# 1.net
KiCad netlist of a schematic drawn in Altium Designer
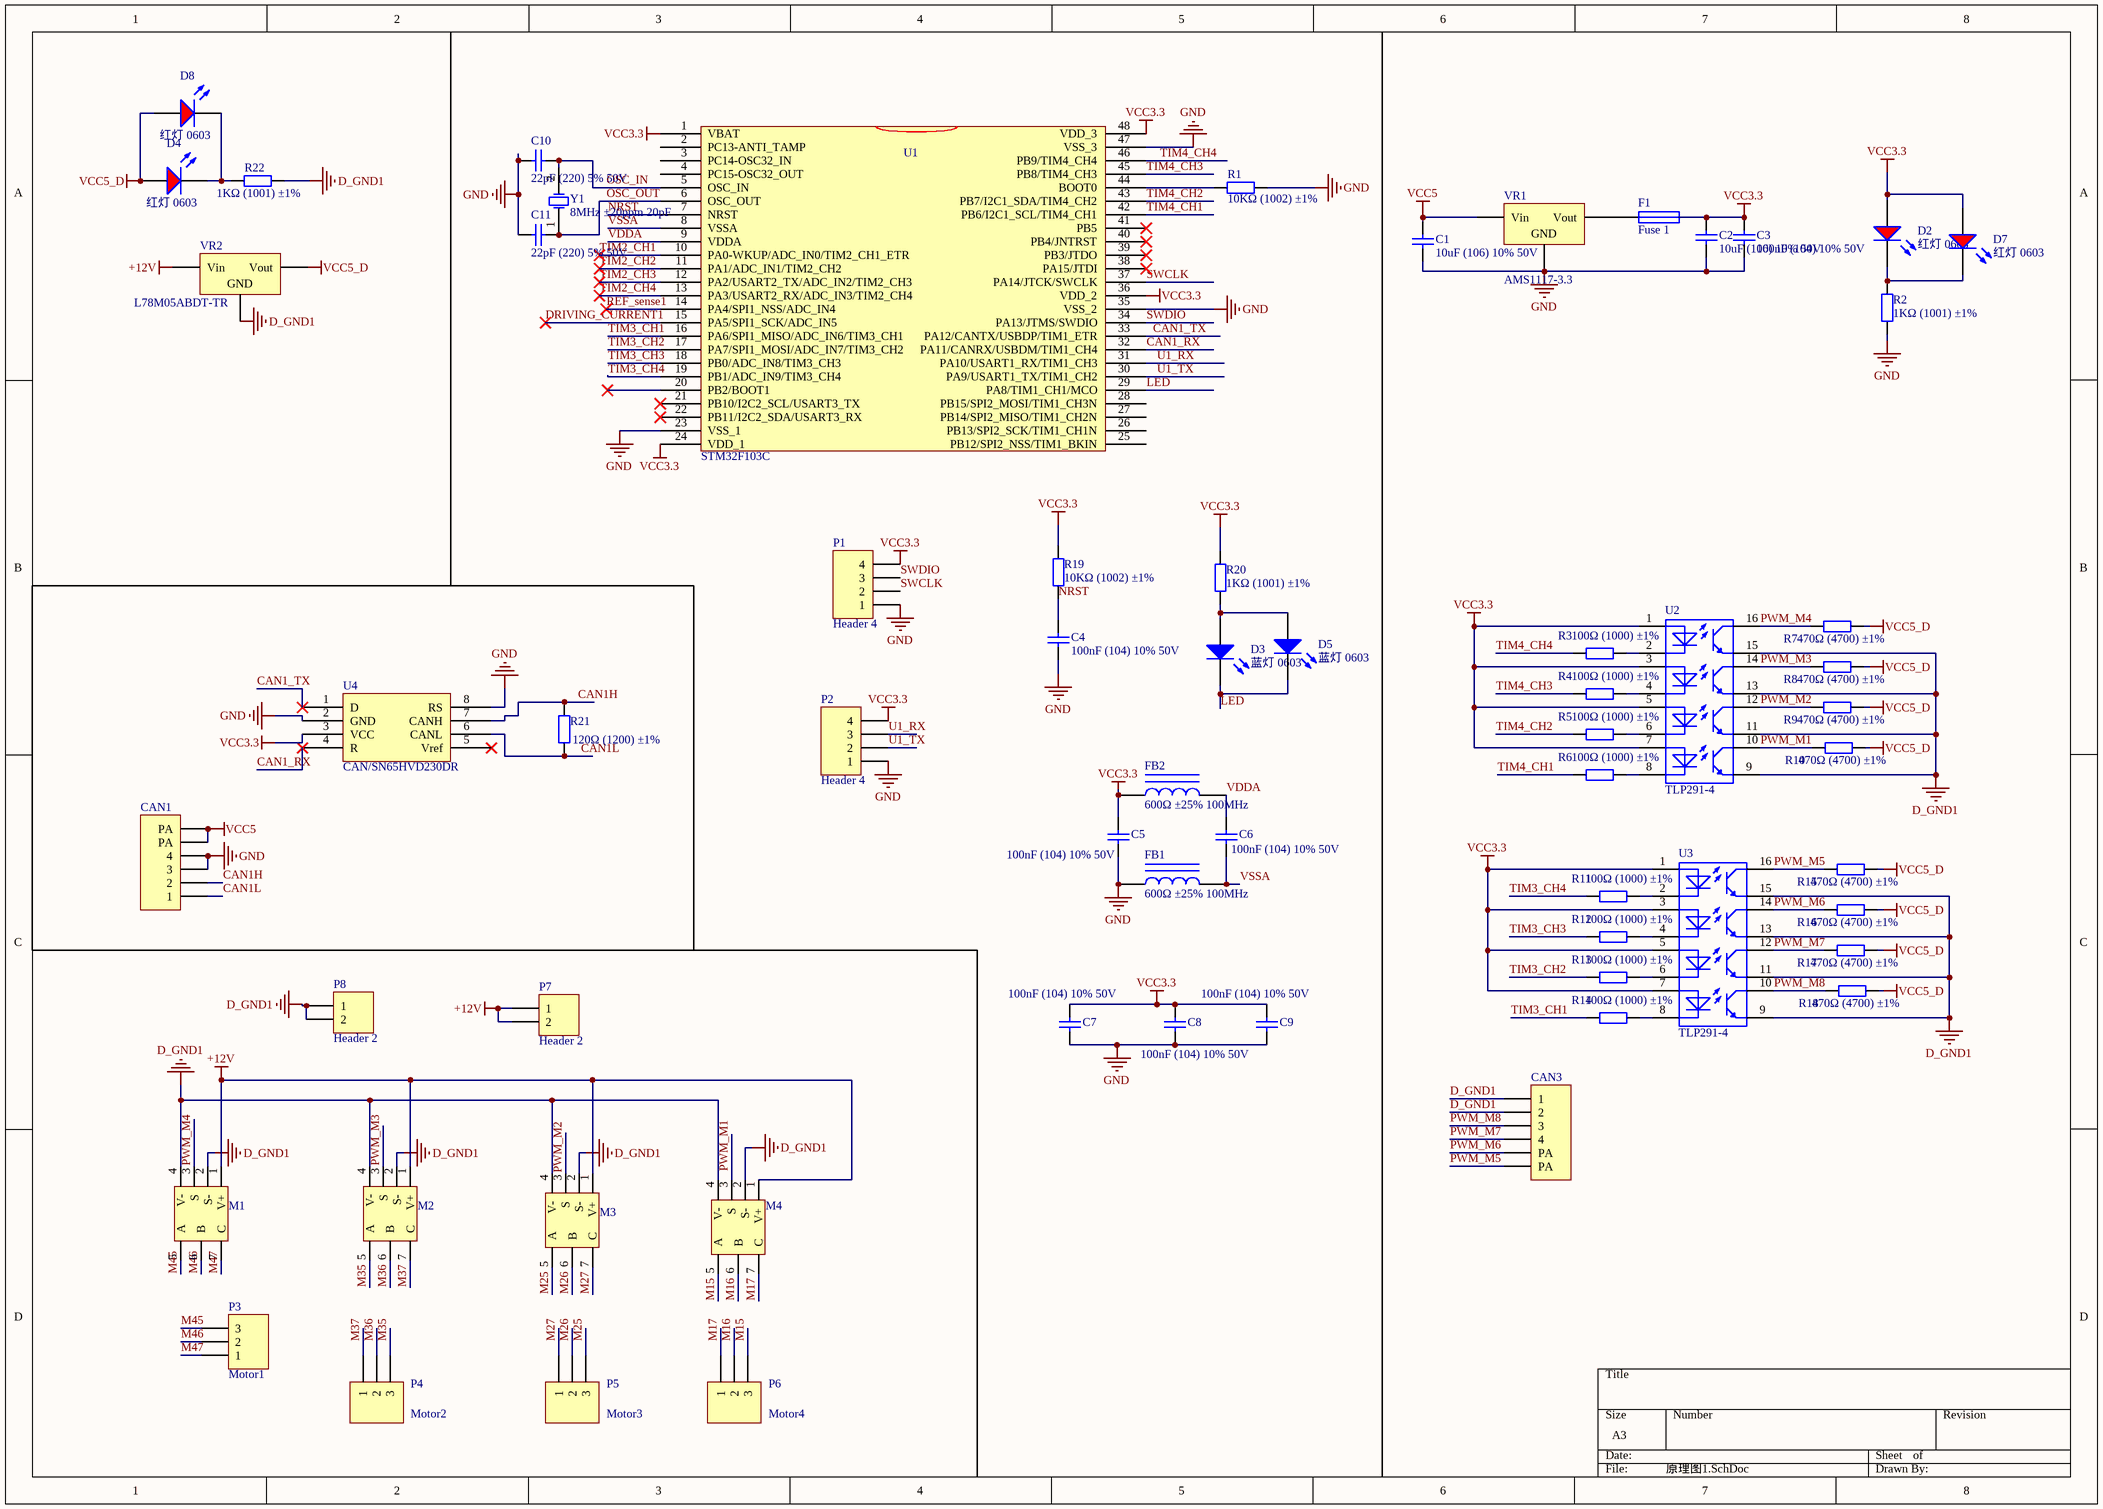
[diagram p0: 原理图1.SchDoc]

(export (version "E")
  (design (tool "Eeschema 10.0.6"))
  (components
    (comp (ref "C1")
      (value "10uF (106) 10% 50V")
      (footprint "0603_C")
      (description "贴片电容")
      (libsource (lib "Miscellaneous Devices LC") (part "1206 10uF (106) 10% 50V"))
    )
    (comp (ref "C2")
      (value "10uF (106) 10% 50V")
      (footprint "0603_C")
      (description "贴片电容")
      (libsource (lib "Miscellaneous Devices LC") (part "1206 10uF (106) 10% 50V"))
    )
    (comp (ref "C3")
      (value "100nF (104) 10% 50V")
      (footprint "0603_C")
      (description "贴片电容")
      (libsource (lib "Miscellaneous Devices LC") (part "0603 100nF (104) 10% 50V"))
    )
    (comp (ref "C4")
      (value "100nF (104) 10% 50V")
      (footprint "0603_C")
      (description "贴片电容")
      (libsource (lib "Miscellaneous Devices LC") (part "0603 100nF (104) 10% 50V"))
    )
    (comp (ref "C5")
      (value "100nF (104) 10% 50V")
      (footprint "0603_C")
      (description "贴片电容")
      (libsource (lib "Miscellaneous Devices LC") (part "0603 100nF (104) 10% 50V"))
    )
    (comp (ref "C6")
      (value "100nF (104) 10% 50V")
      (footprint "0603_C")
      (description "贴片电容")
      (libsource (lib "Miscellaneous Devices LC") (part "0603 100nF (104) 10% 50V"))
    )
    (comp (ref "C7")
      (value "100nF (104) 10% 50V")
      (footprint "0603_C")
      (description "贴片电容")
      (libsource (lib "Miscellaneous Devices LC") (part "0603 100nF (104) 10% 50V"))
    )
    (comp (ref "C8")
      (value "100nF (104) 10% 50V")
      (footprint "0603_C")
      (description "贴片电容")
      (libsource (lib "Miscellaneous Devices LC") (part "0603 100nF (104) 10% 50V"))
    )
    (comp (ref "C9")
      (value "100nF (104) 10% 50V")
      (footprint "0603_C")
      (description "贴片电容")
      (libsource (lib "Miscellaneous Devices LC") (part "0603 100nF (104) 10% 50V"))
    )
    (comp (ref "C10")
      (value "22pF (220) 5% 50V")
      (footprint "0603_C")
      (description "贴片电容")
      (libsource (lib "AD封装2018.9.19Miscellaneous Devices LC") (part "0805 22pF (220) 5% 50V"))
    )
    (comp (ref "C11")
      (value "22pF (220) 5% 50V")
      (footprint "0603_C")
      (description "贴片电容")
      (libsource (lib "AD封装2018.9.19Miscellaneous Devices LC") (part "0805 22pF (220) 5% 50V"))
    )
    (comp (ref "CAN1")
      (value "Header 6")
      (footprint "Modolex_6P")
      (description "Header, 6-Pin")
      (fields (field (name "PUBLISHER") "Altium Limited"))
      (libsource (lib "roobmaster_1") (part "Header 6"))
    )
    (comp (ref "CAN3")
      (value "Header 6")
      (footprint "Modolex_6P")
      (description "Header, 6-Pin")
      (fields (field (name "PUBLISHER") "Altium Limited"))
      (libsource (lib "无刷电机驱动") (part "Header 6"))
    )
    (comp (ref "D2")
      (value "红灯 0603")
      (footprint "0603_LED_S1")
      (description "发光二极管")
      (libsource (lib "Miscellaneous Devices LC") (part "0603 红灯"))
    )
    (comp (ref "D3")
      (value "蓝灯 0603")
      (footprint "0603_LED_S1")
      (description "发光二极管")
      (libsource (lib "Miscellaneous Devices LC") (part "0603 蓝灯"))
    )
    (comp (ref "D4")
      (value "红灯 0603")
      (footprint "0603_LED_S1")
      (description "发光二极管")
      (libsource (lib "Miscellaneous Devices LC") (part "0603 红灯"))
    )
    (comp (ref "D5")
      (value "蓝灯 0603")
      (footprint "0603_LED_S1")
      (description "发光二极管")
      (libsource (lib "Miscellaneous Devices LC") (part "0603 蓝灯"))
    )
    (comp (ref "D7")
      (value "红灯 0603")
      (footprint "0603_LED_S1")
      (description "发光二极管")
      (libsource (lib "Miscellaneous Devices LC") (part "0603 红灯"))
    )
    (comp (ref "D8")
      (value "红灯 0603")
      (footprint "0603_LED_S1")
      (description "发光二极管")
      (libsource (lib "Miscellaneous Devices LC") (part "0603 红灯"))
    )
    (comp (ref "F1")
      (value "Fuse 1")
      (footprint "6-0805_M")
      (description "Fuse")
      (fields (field (name "PUBLISHER") "Altium Limited"))
      (libsource (lib "Miscellaneous Devices") (part "Fuse 1"))
    )
    (comp (ref "FB1")
      (value "600Ω ±25% 100MHz")
      (footprint "0603_L")
      (description "贴片磁珠")
      (libsource (lib "Miscellaneous Devices LC") (part "0805 600Ω 25% 100MHz"))
    )
    (comp (ref "FB2")
      (value "600Ω ±25% 100MHz")
      (footprint "0603_L")
      (description "贴片磁珠")
      (libsource (lib "Miscellaneous Devices LC") (part "0805 600Ω 25% 100MHz"))
    )
    (comp (ref "M1")
      (value "HOBBYWING_FPV")
      (footprint "HOBBYWING_WING20A/30A")
      (libsource (lib "无刷电机驱动") (part "HOBBYWING_FPV"))
    )
    (comp (ref "M2")
      (value "HOBBYWING_FPV")
      (footprint "HOBBYWING_WING20A/30A")
      (libsource (lib "无刷电机驱动") (part "HOBBYWING_FPV"))
    )
    (comp (ref "M3")
      (value "HOBBYWING_FPV")
      (footprint "HOBBYWING_WING20A/30A")
      (libsource (lib "无刷电机驱动") (part "HOBBYWING_FPV"))
    )
    (comp (ref "M4")
      (value "~")
      (footprint "HOBBYWING_WING20A/30A")
      (libsource (lib "无刷电机驱动20180528") (part "HOBBYWING_FPV"))
    )
    (comp (ref "P1")
      (value "Header 4")
      (footprint "Molex-4")
      (description "Header, 4-Pin")
      (fields (field (name "PUBLISHER") "Altium Limited"))
      (libsource (lib "Miscellaneous Connectors") (part "Header 4"))
    )
    (comp (ref "P2")
      (value "Header 4")
      (footprint "Molex-4")
      (description "Header, 4-Pin")
      (fields (field (name "PUBLISHER") "Altium Limited"))
      (libsource (lib "Miscellaneous Connectors") (part "Header 4"))
    )
    (comp (ref "P3")
      (value "Motor1")
      (footprint "11:1")
      (description "Header, 3-Pin")
      (fields (field (name "PUBLISHER") "Altium Limited"))
      (libsource (lib "") (part "Header 3_1"))
    )
    (comp (ref "P4")
      (value "Motor2")
      (footprint "11:1")
      (description "Header, 3-Pin")
      (fields (field (name "PUBLISHER") "Altium Limited"))
      (libsource (lib "Miscellaneous Connectors") (part "Header 3"))
    )
    (comp (ref "P5")
      (value "Motor3")
      (footprint "11:1")
      (description "Header, 3-Pin")
      (fields (field (name "PUBLISHER") "Altium Limited"))
      (libsource (lib "Miscellaneous Connectors") (part "Header 3"))
    )
    (comp (ref "P6")
      (value "Motor4")
      (footprint "11:1")
      (description "Header, 3-Pin")
      (fields (field (name "PUBLISHER") "Altium Limited"))
      (libsource (lib "Miscellaneous Connectors") (part "Header 3"))
    )
    (comp (ref "P7")
      (value "Header 2")
      (footprint "XT30 - 2")
      (description "Header, 2-Pin")
      (fields (field (name "PUBLISHER") "Altium Limited"))
      (libsource (lib "Miscellaneous Connectors") (part "Header 2"))
    )
    (comp (ref "P8")
      (value "Header 2")
      (footprint "XT30 - 2")
      (description "Header, 2-Pin")
      (fields (field (name "PUBLISHER") "Altium Limited"))
      (libsource (lib "Miscellaneous Connectors") (part "Header 2"))
    )
    (comp (ref "R1")
      (value "10KΩ (1002) ±1%")
      (footprint "0603_R")
      (description "贴片电阻")
      (libsource (lib "") (part "0603 10KΩ (1002) 1%_1"))
    )
    (comp (ref "R2")
      (value "1KΩ (1001) ±1%")
      (footprint "0603_R")
      (description "贴片电阻")
      (libsource (lib "") (part "0603 1KΩ (1001) 1%_1"))
    )
    (comp (ref "R3")
      (value "100Ω (1000) ±1%")
      (footprint "0603_R")
      (description "贴片电阻")
      (libsource (lib "Miscellaneous Devices LC") (part "0603 100Ω (1000) 1%"))
    )
    (comp (ref "R4")
      (value "100Ω (1000) ±1%")
      (footprint "0603_R")
      (description "贴片电阻")
      (libsource (lib "Miscellaneous Devices LC") (part "0603 100Ω (1000) 1%"))
    )
    (comp (ref "R5")
      (value "100Ω (1000) ±1%")
      (footprint "0603_R")
      (description "贴片电阻")
      (libsource (lib "Miscellaneous Devices LC") (part "0603 100Ω (1000) 1%"))
    )
    (comp (ref "R6")
      (value "100Ω (1000) ±1%")
      (footprint "0603_R")
      (description "贴片电阻")
      (libsource (lib "Miscellaneous Devices LC") (part "0603 100Ω (1000) 1%"))
    )
    (comp (ref "R7")
      (value "470Ω (4700) ±1%")
      (footprint "0603_R")
      (description "贴片电阻")
      (libsource (lib "Miscellaneous Devices LC") (part "0603 470Ω (4700) 1%"))
    )
    (comp (ref "R8")
      (value "470Ω (4700) ±1%")
      (footprint "0603_R")
      (description "贴片电阻")
      (libsource (lib "Miscellaneous Devices LC") (part "0603 470Ω (4700) 1%"))
    )
    (comp (ref "R9")
      (value "470Ω (4700) ±1%")
      (footprint "0603_R")
      (description "贴片电阻")
      (libsource (lib "Miscellaneous Devices LC") (part "0603 470Ω (4700) 1%"))
    )
    (comp (ref "R10")
      (value "470Ω (4700) ±1%")
      (footprint "0603_R")
      (description "贴片电阻")
      (libsource (lib "Miscellaneous Devices LC") (part "0603 470Ω (4700) 1%"))
    )
    (comp (ref "R11")
      (value "100Ω (1000) ±1%")
      (footprint "0603_R")
      (description "贴片电阻")
      (libsource (lib "Miscellaneous Devices LC") (part "0603 100Ω (1000) 1%"))
    )
    (comp (ref "R12")
      (value "100Ω (1000) ±1%")
      (footprint "0603_R")
      (description "贴片电阻")
      (libsource (lib "Miscellaneous Devices LC") (part "0603 100Ω (1000) 1%"))
    )
    (comp (ref "R13")
      (value "100Ω (1000) ±1%")
      (footprint "0603_R")
      (description "贴片电阻")
      (libsource (lib "Miscellaneous Devices LC") (part "0603 100Ω (1000) 1%"))
    )
    (comp (ref "R14")
      (value "100Ω (1000) ±1%")
      (footprint "0603_R")
      (description "贴片电阻")
      (libsource (lib "Miscellaneous Devices LC") (part "0603 100Ω (1000) 1%"))
    )
    (comp (ref "R15")
      (value "470Ω (4700) ±1%")
      (footprint "0603_R")
      (description "贴片电阻")
      (libsource (lib "Miscellaneous Devices LC") (part "0603 470Ω (4700) 1%"))
    )
    (comp (ref "R16")
      (value "470Ω (4700) ±1%")
      (footprint "0603_R")
      (description "贴片电阻")
      (libsource (lib "Miscellaneous Devices LC") (part "0603 470Ω (4700) 1%"))
    )
    (comp (ref "R17")
      (value "470Ω (4700) ±1%")
      (footprint "0603_R")
      (description "贴片电阻")
      (libsource (lib "Miscellaneous Devices LC") (part "0603 470Ω (4700) 1%"))
    )
    (comp (ref "R18")
      (value "470Ω (4700) ±1%")
      (footprint "0603_R")
      (description "贴片电阻")
      (libsource (lib "Miscellaneous Devices LC") (part "0603 470Ω (4700) 1%"))
    )
    (comp (ref "R19")
      (value "10KΩ (1002) ±1%")
      (footprint "0603_R")
      (description "贴片电阻")
      (libsource (lib "Miscellaneous Devices LC") (part "0603 10KΩ (1002) 1%"))
    )
    (comp (ref "R20")
      (value "1KΩ (1001) ±1%")
      (footprint "0603_R")
      (description "贴片电阻")
      (libsource (lib "") (part "0603 1KΩ (1001) 1%_1"))
    )
    (comp (ref "R21")
      (value "120Ω (1200) ±1%")
      (footprint "0603_R")
      (description "贴片电阻")
      (libsource (lib "Miscellaneous Devices LC") (part "0603 120Ω (1200) 1%"))
    )
    (comp (ref "R22")
      (value "1KΩ (1001) ±1%")
      (footprint "0603_R")
      (description "贴片电阻")
      (libsource (lib "Miscellaneous Devices LC") (part "0603 1KΩ (1001) 1%"))
    )
    (comp (ref "U1")
      (value "STM32F103C")
      (footprint "LQFP-48_7x7x05P")
      (libsource (lib "my_lib") (part "STM32F103C"))
    )
    (comp (ref "U2")
      (value "TLP291-4")
      (footprint "LC-SOP-16_150mil")
      (libsource (lib "XQ_Library") (part "TLP521-4"))
    )
    (comp (ref "U3")
      (value "TLP291-4")
      (footprint "LC-SOP-16_150mil")
      (libsource (lib "XQ_Library") (part "TLP521-4"))
    )
    (comp (ref "U4")
      (value "CAN/SN65HVD230DR")
      (footprint "SOIC-8_150mil")
      (description "CAN")
      (libsource (lib "AD封装2018.9.19Miscellaneous Devices LC") (part "CAN/SN65HVD230DR_[C12084]"))
    )
    (comp (ref "VR1")
      (value "AMS1117-3.3")
      (footprint "SOT-223")
      (description "低压差线性稳压(LDO)")
      (libsource (lib "Miscellaneous Devices LC") (part "SOT-223 AMS1117-3.3"))
    )
    (comp (ref "VR2")
      (value "L78M05ABDT-TR")
      (footprint "TO-252-2-180")
      (description "低压差线性稳压(LDO)")
      (libsource (lib "Miscellaneous Devices LC") (part "TO-252-2 L78M05ABDT-TR"))
    )
    (comp (ref "Y1")
      (value "8MHz ±20ppm 20pF")
      (footprint "SMD-5032_2P")
      (description "贴片晶振")
      (libsource (lib "AD封装2018.9.19Miscellaneous Devices LC") (part "SMD-5032_2P 8MHz 20ppm 20pF"))
    )
  )
  (nets
    (net (code "1") (name "+12V") (class "Default")
      (node (ref "M1") (pin "1") (pinfunction "V+_1") (pintype "passive"))
      (node (ref "M2") (pin "1") (pinfunction "V+_1") (pintype "passive"))
      (node (ref "M3") (pin "1") (pinfunction "V+_1") (pintype "passive"))
      (node (ref "M4") (pin "1") (pinfunction "V+_1") (pintype "passive"))
      (node (ref "P7") (pin "1") (pinfunction "1_1") (pintype "passive"))
      (node (ref "P7") (pin "2") (pinfunction "2_2") (pintype "passive"))
      (node (ref "VR2") (pin "1") (pinfunction "Vin_1") (pintype "passive"))
    )
    (net (code "2") (name "/CAN1H") (class "Default")
      (node (ref "CAN1") (pin "2") (pinfunction "2_2") (pintype "passive"))
      (node (ref "R21") (pin "1") (pinfunction "1_1") (pintype "passive"))
      (node (ref "U4") (pin "7") (pinfunction "CANH_7") (pintype "passive"))
    )
    (net (code "3") (name "/CAN1L") (class "Default")
      (node (ref "CAN1") (pin "1") (pinfunction "1_1") (pintype "passive"))
      (node (ref "R21") (pin "2") (pinfunction "2_2") (pintype "passive"))
      (node (ref "U4") (pin "6") (pinfunction "CANL_6") (pintype "passive"))
    )
    (net (code "4") (name "/CAN1_RX") (class "Default")
      (node (ref "U1") (pin "32") (pinfunction "PA11/CANRX/USBDM/TIM1_CH4_32") (pintype "passive"))
      (node (ref "U4") (pin "4") (pinfunction "R_4") (pintype "passive"))
    )
    (net (code "5") (name "/CAN1_TX") (class "Default")
      (node (ref "U1") (pin "33") (pinfunction "PA12/CANTX/USBDP/TIM1_ETR_33") (pintype "passive"))
      (node (ref "U4") (pin "1") (pinfunction "D_1") (pintype "passive"))
    )
    (net (code "6") (name "/DRIVING_CURRENT1") (class "Default")
      (node (ref "U1") (pin "15") (pinfunction "PA5/SPI1_SCK/ADC_IN5_15") (pintype "passive+no_connect"))
    )
    (net (code "7") (name "/LED") (class "Default")
      (node (ref "D3") (pin "K") (pinfunction "K_K") (pintype "passive"))
      (node (ref "D5") (pin "K") (pinfunction "K_K") (pintype "passive"))
      (node (ref "U1") (pin "29") (pinfunction "PA8/TIM1_CH1/MCO_29") (pintype "passive"))
    )
    (net (code "8") (name "/M15") (class "Default")
      (node (ref "M4") (pin "5") (pinfunction "A_5") (pintype "passive"))
      (node (ref "P6") (pin "3") (pinfunction "3_3") (pintype "passive"))
    )
    (net (code "9") (name "/M16") (class "Default")
      (node (ref "M4") (pin "6") (pinfunction "B_6") (pintype "passive"))
      (node (ref "P6") (pin "2") (pinfunction "2_2") (pintype "passive"))
    )
    (net (code "10") (name "/M17") (class "Default")
      (node (ref "M4") (pin "7") (pinfunction "C_7") (pintype "passive"))
      (node (ref "P6") (pin "1") (pinfunction "1_1") (pintype "passive"))
    )
    (net (code "11") (name "/M25") (class "Default")
      (node (ref "M3") (pin "5") (pinfunction "A_5") (pintype "passive"))
      (node (ref "P5") (pin "3") (pinfunction "3_3") (pintype "passive"))
    )
    (net (code "12") (name "/M26") (class "Default")
      (node (ref "M3") (pin "6") (pinfunction "B_6") (pintype "passive"))
      (node (ref "P5") (pin "2") (pinfunction "2_2") (pintype "passive"))
    )
    (net (code "13") (name "/M27") (class "Default")
      (node (ref "M3") (pin "7") (pinfunction "C_7") (pintype "passive"))
      (node (ref "P5") (pin "1") (pinfunction "1_1") (pintype "passive"))
    )
    (net (code "14") (name "/M35") (class "Default")
      (node (ref "M2") (pin "5") (pinfunction "A_5") (pintype "passive"))
      (node (ref "P4") (pin "3") (pinfunction "3_3") (pintype "passive"))
    )
    (net (code "15") (name "/M36") (class "Default")
      (node (ref "M2") (pin "6") (pinfunction "B_6") (pintype "passive"))
      (node (ref "P4") (pin "2") (pinfunction "2_2") (pintype "passive"))
    )
    (net (code "16") (name "/M37") (class "Default")
      (node (ref "M2") (pin "7") (pinfunction "C_7") (pintype "passive"))
      (node (ref "P4") (pin "1") (pinfunction "1_1") (pintype "passive"))
    )
    (net (code "17") (name "/M45") (class "Default")
      (node (ref "M1") (pin "5") (pinfunction "A_5") (pintype "passive"))
      (node (ref "P3") (pin "3") (pinfunction "3_3") (pintype "passive"))
    )
    (net (code "18") (name "/M46") (class "Default")
      (node (ref "M1") (pin "6") (pinfunction "B_6") (pintype "passive"))
      (node (ref "P3") (pin "2") (pinfunction "2_2") (pintype "passive"))
    )
    (net (code "19") (name "/M47") (class "Default")
      (node (ref "M1") (pin "7") (pinfunction "C_7") (pintype "passive"))
      (node (ref "P3") (pin "1") (pinfunction "1_1") (pintype "passive"))
    )
    (net (code "20") (name "/NRST") (class "Default")
      (node (ref "C4") (pin "2") (pinfunction "2_2") (pintype "passive"))
      (node (ref "R19") (pin "1") (pinfunction "1_1") (pintype "passive"))
      (node (ref "U1") (pin "7") (pinfunction "NRST_7") (pintype "passive"))
    )
    (net (code "21") (name "/OSC_IN") (class "Default")
      (node (ref "C10") (pin "2") (pinfunction "2_2") (pintype "passive"))
      (node (ref "U1") (pin "5") (pinfunction "OSC_IN_5") (pintype "passive"))
      (node (ref "Y1") (pin "2") (pinfunction "OSC2_2") (pintype "passive"))
    )
    (net (code "22") (name "/OSC_OUT") (class "Default")
      (node (ref "C11") (pin "2") (pinfunction "2_2") (pintype "passive"))
      (node (ref "U1") (pin "6") (pinfunction "OSC_OUT_6") (pintype "passive"))
      (node (ref "Y1") (pin "1") (pinfunction "OSC1_1") (pintype "passive"))
    )
    (net (code "23") (name "/PWM_M1") (class "Default")
      (node (ref "M4") (pin "3") (pinfunction "S_3") (pintype "passive"))
      (node (ref "R10") (pin "1") (pinfunction "1_1") (pintype "passive"))
      (node (ref "U2") (pin "10") (pinfunction "10_10") (pintype "passive"))
    )
    (net (code "24") (name "/PWM_M2") (class "Default")
      (node (ref "M3") (pin "3") (pinfunction "S_3") (pintype "passive"))
      (node (ref "R9") (pin "1") (pinfunction "1_1") (pintype "passive"))
      (node (ref "U2") (pin "12") (pinfunction "12_12") (pintype "passive"))
    )
    (net (code "25") (name "/PWM_M3") (class "Default")
      (node (ref "M2") (pin "3") (pinfunction "S_3") (pintype "passive"))
      (node (ref "R8") (pin "1") (pinfunction "1_1") (pintype "passive"))
      (node (ref "U2") (pin "14") (pinfunction "14_14") (pintype "passive"))
    )
    (net (code "26") (name "/PWM_M4") (class "Default")
      (node (ref "M1") (pin "3") (pinfunction "S_3") (pintype "passive"))
      (node (ref "R7") (pin "1") (pinfunction "1_1") (pintype "passive"))
      (node (ref "U2") (pin "16") (pinfunction "16_16") (pintype "passive"))
    )
    (net (code "27") (name "/PWM_M5") (class "Default")
      (node (ref "CAN3") (pin "6") (pinfunction "PA_6") (pintype "passive"))
      (node (ref "R15") (pin "1") (pinfunction "1_1") (pintype "passive"))
      (node (ref "U3") (pin "16") (pinfunction "16_16") (pintype "passive"))
    )
    (net (code "28") (name "/PWM_M6") (class "Default")
      (node (ref "CAN3") (pin "5") (pinfunction "PA_5") (pintype "passive"))
      (node (ref "R16") (pin "1") (pinfunction "1_1") (pintype "passive"))
      (node (ref "U3") (pin "14") (pinfunction "14_14") (pintype "passive"))
    )
    (net (code "29") (name "/PWM_M7") (class "Default")
      (node (ref "CAN3") (pin "4") (pinfunction "4_4") (pintype "passive"))
      (node (ref "R17") (pin "1") (pinfunction "1_1") (pintype "passive"))
      (node (ref "U3") (pin "12") (pinfunction "12_12") (pintype "passive"))
    )
    (net (code "30") (name "/PWM_M8") (class "Default")
      (node (ref "CAN3") (pin "3") (pinfunction "3_3") (pintype "passive"))
      (node (ref "R18") (pin "1") (pinfunction "1_1") (pintype "passive"))
      (node (ref "U3") (pin "10") (pinfunction "10_10") (pintype "passive"))
    )
    (net (code "31") (name "/REF_sense1") (class "Default")
      (node (ref "U1") (pin "14") (pinfunction "PA4/SPI1_NSS/ADC_IN4_14") (pintype "passive+no_connect"))
    )
    (net (code "32") (name "/SWCLK") (class "Default")
      (node (ref "P1") (pin "2") (pinfunction "2_2") (pintype "passive"))
      (node (ref "U1") (pin "37") (pinfunction "PA14/JTCK/SWCLK_37") (pintype "passive"))
    )
    (net (code "33") (name "/SWDIO") (class "Default")
      (node (ref "P1") (pin "3") (pinfunction "3_3") (pintype "passive"))
      (node (ref "U1") (pin "34") (pinfunction "PA13/JTMS/SWDIO_34") (pintype "passive"))
    )
    (net (code "34") (name "/TIM2_CH1") (class "Default")
      (node (ref "U1") (pin "10") (pinfunction "PA0-WKUP/ADC_IN0/TIM2_CH1_ETR_10") (pintype "passive+no_connect"))
    )
    (net (code "35") (name "/TIM2_CH2") (class "Default")
      (node (ref "U1") (pin "11") (pinfunction "PA1/ADC_IN1/TIM2_CH2_11") (pintype "passive+no_connect"))
    )
    (net (code "36") (name "/TIM2_CH3") (class "Default")
      (node (ref "U1") (pin "12") (pinfunction "PA2/USART2_TX/ADC_IN2/TIM2_CH3_12") (pintype "passive+no_connect"))
    )
    (net (code "37") (name "/TIM2_CH4") (class "Default")
      (node (ref "U1") (pin "13") (pinfunction "PA3/USART2_RX/ADC_IN3/TIM2_CH4_13") (pintype "passive+no_connect"))
    )
    (net (code "38") (name "/TIM3_CH1") (class "Default")
      (node (ref "R14") (pin "1") (pinfunction "1_1") (pintype "passive"))
      (node (ref "U1") (pin "16") (pinfunction "PA6/SPI1_MISO/ADC_IN6/TIM3_CH1_16") (pintype "passive"))
    )
    (net (code "39") (name "/TIM3_CH2") (class "Default")
      (node (ref "R13") (pin "1") (pinfunction "1_1") (pintype "passive"))
      (node (ref "U1") (pin "17") (pinfunction "PA7/SPI1_MOSI/ADC_IN7/TIM3_CH2_17") (pintype "passive"))
    )
    (net (code "40") (name "/TIM3_CH3") (class "Default")
      (node (ref "R12") (pin "1") (pinfunction "1_1") (pintype "passive"))
      (node (ref "U1") (pin "18") (pinfunction "PB0/ADC_IN8/TIM3_CH3_18") (pintype "passive"))
    )
    (net (code "41") (name "/TIM3_CH4") (class "Default")
      (node (ref "R11") (pin "1") (pinfunction "1_1") (pintype "passive"))
      (node (ref "U1") (pin "19") (pinfunction "PB1/ADC_IN9/TIM3_CH4_19") (pintype "passive"))
    )
    (net (code "42") (name "/TIM4_CH1") (class "Default")
      (node (ref "R6") (pin "1") (pinfunction "1_1") (pintype "passive"))
      (node (ref "U1") (pin "42") (pinfunction "PB6/I2C1_SCL/TIM4_CH1_42") (pintype "passive"))
    )
    (net (code "43") (name "/TIM4_CH2") (class "Default")
      (node (ref "R5") (pin "1") (pinfunction "1_1") (pintype "passive"))
      (node (ref "U1") (pin "43") (pinfunction "PB7/I2C1_SDA/TIM4_CH2_43") (pintype "passive"))
    )
    (net (code "44") (name "/TIM4_CH3") (class "Default")
      (node (ref "R4") (pin "1") (pinfunction "1_1") (pintype "passive"))
      (node (ref "U1") (pin "45") (pinfunction "PB8/TIM4_CH3_45") (pintype "passive"))
    )
    (net (code "45") (name "/TIM4_CH4") (class "Default")
      (node (ref "R3") (pin "1") (pinfunction "1_1") (pintype "passive"))
      (node (ref "U1") (pin "46") (pinfunction "PB9/TIM4_CH4_46") (pintype "passive"))
    )
    (net (code "46") (name "/U1_RX") (class "Default")
      (node (ref "P2") (pin "3") (pinfunction "3_3") (pintype "passive"))
      (node (ref "U1") (pin "31") (pinfunction "PA10/USART1_RX/TIM1_CH3_31") (pintype "passive"))
    )
    (net (code "47") (name "/U1_TX") (class "Default")
      (node (ref "P2") (pin "2") (pinfunction "2_2") (pintype "passive"))
      (node (ref "U1") (pin "30") (pinfunction "PA9/USART1_TX/TIM1_CH2_30") (pintype "passive"))
    )
    (net (code "48") (name "/VDDA") (class "Default")
      (node (ref "C6") (pin "2") (pinfunction "2_2") (pintype "passive"))
      (node (ref "FB2") (pin "2") (pinfunction "2_2") (pintype "passive"))
      (node (ref "U1") (pin "9") (pinfunction "VDDA_9") (pintype "passive"))
    )
    (net (code "49") (name "/VSSA") (class "Default")
      (node (ref "C6") (pin "1") (pinfunction "1_1") (pintype "passive"))
      (node (ref "FB1") (pin "2") (pinfunction "2_2") (pintype "passive"))
      (node (ref "U1") (pin "8") (pinfunction "VSSA_8") (pintype "passive"))
    )
    (net (code "50") (name "D_GND1") (class "Default")
      (node (ref "CAN3") (pin "1") (pinfunction "1_1") (pintype "passive"))
      (node (ref "CAN3") (pin "2") (pinfunction "2_2") (pintype "passive"))
      (node (ref "M1") (pin "2") (pinfunction "S-_2") (pintype "passive"))
      (node (ref "M1") (pin "4") (pinfunction "V-_4") (pintype "passive"))
      (node (ref "M2") (pin "2") (pinfunction "S-_2") (pintype "passive"))
      (node (ref "M2") (pin "4") (pinfunction "V-_4") (pintype "passive"))
      (node (ref "M3") (pin "2") (pinfunction "S-_2") (pintype "passive"))
      (node (ref "M3") (pin "4") (pinfunction "V-_4") (pintype "passive"))
      (node (ref "M4") (pin "2") (pinfunction "S-_2") (pintype "passive"))
      (node (ref "M4") (pin "4") (pinfunction "V-_4") (pintype "passive"))
      (node (ref "P8") (pin "1") (pinfunction "1_1") (pintype "passive"))
      (node (ref "P8") (pin "2") (pinfunction "2_2") (pintype "passive"))
      (node (ref "R22") (pin "1") (pinfunction "1_1") (pintype "passive"))
      (node (ref "U2") (pin "11") (pinfunction "11_11") (pintype "passive"))
      (node (ref "U2") (pin "13") (pinfunction "13_13") (pintype "passive"))
      (node (ref "U2") (pin "15") (pinfunction "15_15") (pintype "passive"))
      (node (ref "U2") (pin "9") (pinfunction "9_9") (pintype "passive"))
      (node (ref "U3") (pin "11") (pinfunction "11_11") (pintype "passive"))
      (node (ref "U3") (pin "13") (pinfunction "13_13") (pintype "passive"))
      (node (ref "U3") (pin "15") (pinfunction "15_15") (pintype "passive"))
      (node (ref "U3") (pin "9") (pinfunction "9_9") (pintype "passive"))
      (node (ref "VR2") (pin "2") (pinfunction "GND_2") (pintype "passive"))
    )
    (net (code "51") (name "GND") (class "Default")
      (node (ref "C1") (pin "1") (pinfunction "1_1") (pintype "passive"))
      (node (ref "C10") (pin "1") (pinfunction "1_1") (pintype "passive"))
      (node (ref "C11") (pin "1") (pinfunction "1_1") (pintype "passive"))
      (node (ref "C2") (pin "1") (pinfunction "1_1") (pintype "passive"))
      (node (ref "C3") (pin "1") (pinfunction "1_1") (pintype "passive"))
      (node (ref "C4") (pin "1") (pinfunction "1_1") (pintype "passive"))
      (node (ref "C5") (pin "1") (pinfunction "1_1") (pintype "passive"))
      (node (ref "C7") (pin "1") (pinfunction "1_1") (pintype "passive"))
      (node (ref "C8") (pin "1") (pinfunction "1_1") (pintype "passive"))
      (node (ref "C9") (pin "1") (pinfunction "1_1") (pintype "passive"))
      (node (ref "CAN1") (pin "3") (pinfunction "3_3") (pintype "passive"))
      (node (ref "CAN1") (pin "4") (pinfunction "4_4") (pintype "passive"))
      (node (ref "FB1") (pin "1") (pinfunction "1_1") (pintype "passive"))
      (node (ref "P1") (pin "1") (pinfunction "1_1") (pintype "passive"))
      (node (ref "P2") (pin "1") (pinfunction "1_1") (pintype "passive"))
      (node (ref "R1") (pin "1") (pinfunction "1_1") (pintype "passive"))
      (node (ref "R2") (pin "1") (pinfunction "1_1") (pintype "passive"))
      (node (ref "U1") (pin "23") (pinfunction "VSS_1_23") (pintype "passive"))
      (node (ref "U1") (pin "35") (pinfunction "VSS_2_35") (pintype "passive"))
      (node (ref "U1") (pin "47") (pinfunction "VSS_3_47") (pintype "passive"))
      (node (ref "U4") (pin "2") (pinfunction "GND_2") (pintype "passive"))
      (node (ref "U4") (pin "8") (pinfunction "RS_8") (pintype "passive"))
      (node (ref "VR1") (pin "1") (pinfunction "GND_1") (pintype "passive"))
    )
    (net (code "52") (name "Net-(D2-PadK)") (class "Default")
      (node (ref "D2") (pin "K") (pinfunction "K_K") (pintype "passive"))
      (node (ref "D7") (pin "K") (pinfunction "K_K") (pintype "passive"))
      (node (ref "R2") (pin "2") (pinfunction "2_2") (pintype "passive"))
    )
    (net (code "53") (name "Net-(D3-PadA)") (class "Default")
      (node (ref "D3") (pin "A") (pinfunction "A_A") (pintype "passive"))
      (node (ref "D5") (pin "A") (pinfunction "A_A") (pintype "passive"))
      (node (ref "R20") (pin "1") (pinfunction "1_1") (pintype "passive"))
    )
    (net (code "54") (name "Net-(D4-PadK)") (class "Default")
      (node (ref "D4") (pin "K") (pinfunction "K_K") (pintype "passive"))
      (node (ref "D8") (pin "K") (pinfunction "K_K") (pintype "passive"))
      (node (ref "R22") (pin "2") (pinfunction "2_2") (pintype "passive"))
    )
    (net (code "55") (name "Net-(R3-Pad2)") (class "Default")
      (node (ref "R3") (pin "2") (pinfunction "2_2") (pintype "passive"))
      (node (ref "U2") (pin "2") (pinfunction "2_2") (pintype "passive"))
    )
    (net (code "56") (name "Net-(R4-Pad2)") (class "Default")
      (node (ref "R4") (pin "2") (pinfunction "2_2") (pintype "passive"))
      (node (ref "U2") (pin "4") (pinfunction "4_4") (pintype "passive"))
    )
    (net (code "57") (name "Net-(R5-Pad2)") (class "Default")
      (node (ref "R5") (pin "2") (pinfunction "2_2") (pintype "passive"))
      (node (ref "U2") (pin "6") (pinfunction "6_6") (pintype "passive"))
    )
    (net (code "58") (name "Net-(R6-Pad2)") (class "Default")
      (node (ref "R6") (pin "2") (pinfunction "2_2") (pintype "passive"))
      (node (ref "U2") (pin "8") (pinfunction "8_8") (pintype "passive"))
    )
    (net (code "59") (name "Net-(R11-Pad2)") (class "Default")
      (node (ref "R11") (pin "2") (pinfunction "2_2") (pintype "passive"))
      (node (ref "U3") (pin "2") (pinfunction "2_2") (pintype "passive"))
    )
    (net (code "60") (name "Net-(R12-Pad2)") (class "Default")
      (node (ref "R12") (pin "2") (pinfunction "2_2") (pintype "passive"))
      (node (ref "U3") (pin "4") (pinfunction "4_4") (pintype "passive"))
    )
    (net (code "61") (name "Net-(R13-Pad2)") (class "Default")
      (node (ref "R13") (pin "2") (pinfunction "2_2") (pintype "passive"))
      (node (ref "U3") (pin "6") (pinfunction "6_6") (pintype "passive"))
    )
    (net (code "62") (name "Net-(R14-Pad2)") (class "Default")
      (node (ref "R14") (pin "2") (pinfunction "2_2") (pintype "passive"))
      (node (ref "U3") (pin "8") (pinfunction "8_8") (pintype "passive"))
    )
    (net (code "63") (name "Net-(U1-BOOT0)") (class "Default")
      (node (ref "R1") (pin "2") (pinfunction "2_2") (pintype "passive"))
      (node (ref "U1") (pin "44") (pinfunction "BOOT0_44") (pintype "passive"))
    )
    (net (code "64") (name "Net-(VR1-Vout)") (class "Default")
      (node (ref "F1") (pin "1") (pinfunction "1_1") (pintype "passive"))
      (node (ref "VR1") (pin "2") (pinfunction "Vout_2") (pintype "passive"))
    )
    (net (code "65") (name "VCC3.3") (class "Default")
      (node (ref "C2") (pin "2") (pinfunction "2_2") (pintype "passive"))
      (node (ref "C3") (pin "2") (pinfunction "2_2") (pintype "passive"))
      (node (ref "C5") (pin "2") (pinfunction "2_2") (pintype "passive"))
      (node (ref "C7") (pin "2") (pinfunction "2_2") (pintype "passive"))
      (node (ref "C8") (pin "2") (pinfunction "2_2") (pintype "passive"))
      (node (ref "C9") (pin "2") (pinfunction "2_2") (pintype "passive"))
      (node (ref "D2") (pin "A") (pinfunction "A_A") (pintype "passive"))
      (node (ref "D7") (pin "A") (pinfunction "A_A") (pintype "passive"))
      (node (ref "F1") (pin "2") (pinfunction "2_2") (pintype "passive"))
      (node (ref "FB2") (pin "1") (pinfunction "1_1") (pintype "passive"))
      (node (ref "P1") (pin "4") (pinfunction "4_4") (pintype "passive"))
      (node (ref "P2") (pin "4") (pinfunction "4_4") (pintype "passive"))
      (node (ref "R19") (pin "2") (pinfunction "2_2") (pintype "passive"))
      (node (ref "R20") (pin "2") (pinfunction "2_2") (pintype "passive"))
      (node (ref "U1") (pin "1") (pinfunction "VBAT_1") (pintype "passive"))
      (node (ref "U1") (pin "24") (pinfunction "VDD_1_24") (pintype "passive"))
      (node (ref "U1") (pin "36") (pinfunction "VDD_2_36") (pintype "passive"))
      (node (ref "U1") (pin "48") (pinfunction "VDD_3_48") (pintype "passive"))
      (node (ref "U2") (pin "1") (pinfunction "1_1") (pintype "passive"))
      (node (ref "U2") (pin "3") (pinfunction "3_3") (pintype "passive"))
      (node (ref "U2") (pin "5") (pinfunction "5_5") (pintype "passive"))
      (node (ref "U2") (pin "7") (pinfunction "7_7") (pintype "passive"))
      (node (ref "U3") (pin "1") (pinfunction "1_1") (pintype "passive"))
      (node (ref "U3") (pin "3") (pinfunction "3_3") (pintype "passive"))
      (node (ref "U3") (pin "5") (pinfunction "5_5") (pintype "passive"))
      (node (ref "U3") (pin "7") (pinfunction "7_7") (pintype "passive"))
      (node (ref "U4") (pin "3") (pinfunction "VCC_3") (pintype "passive"))
    )
    (net (code "66") (name "VCC5") (class "Default")
      (node (ref "C1") (pin "2") (pinfunction "2_2") (pintype "passive"))
      (node (ref "CAN1") (pin "5") (pinfunction "PA_5") (pintype "passive"))
      (node (ref "CAN1") (pin "6") (pinfunction "PA_6") (pintype "passive"))
      (node (ref "VR1") (pin "3") (pinfunction "Vin_3") (pintype "passive"))
    )
    (net (code "67") (name "VCC5_D") (class "Default")
      (node (ref "D4") (pin "A") (pinfunction "A_A") (pintype "passive"))
      (node (ref "D8") (pin "A") (pinfunction "A_A") (pintype "passive"))
      (node (ref "R10") (pin "2") (pinfunction "2_2") (pintype "passive"))
      (node (ref "R15") (pin "2") (pinfunction "2_2") (pintype "passive"))
      (node (ref "R16") (pin "2") (pinfunction "2_2") (pintype "passive"))
      (node (ref "R17") (pin "2") (pinfunction "2_2") (pintype "passive"))
      (node (ref "R18") (pin "2") (pinfunction "2_2") (pintype "passive"))
      (node (ref "R7") (pin "2") (pinfunction "2_2") (pintype "passive"))
      (node (ref "R8") (pin "2") (pinfunction "2_2") (pintype "passive"))
      (node (ref "R9") (pin "2") (pinfunction "2_2") (pintype "passive"))
      (node (ref "VR2") (pin "3") (pinfunction "Vout_3") (pintype "passive"))
    )
    (net (code "68") (name "unconnected-(U1-PA15{slash}JTDI-Pad38)") (class "Default")
      (node (ref "U1") (pin "38") (pinfunction "PA15/JTDI_38") (pintype "passive+no_connect"))
    )
    (net (code "69") (name "unconnected-(U1-PB2{slash}BOOT1-Pad20)") (class "Default")
      (node (ref "U1") (pin "20") (pinfunction "PB2/BOOT1_20") (pintype "passive+no_connect"))
    )
    (net (code "70") (name "unconnected-(U1-PB3{slash}JTDO-Pad39)") (class "Default")
      (node (ref "U1") (pin "39") (pinfunction "PB3/JTDO_39") (pintype "passive+no_connect"))
    )
    (net (code "71") (name "unconnected-(U1-PB4{slash}JNTRST-Pad40)") (class "Default")
      (node (ref "U1") (pin "40") (pinfunction "PB4/JNTRST_40") (pintype "passive+no_connect"))
    )
    (net (code "72") (name "unconnected-(U1-PB5-Pad41)") (class "Default")
      (node (ref "U1") (pin "41") (pinfunction "PB5_41") (pintype "passive+no_connect"))
    )
    (net (code "73") (name "unconnected-(U1-PB10{slash}I2C2_SCL{slash}USART3_TX-Pad21)") (class "Default")
      (node (ref "U1") (pin "21") (pinfunction "PB10/I2C2_SCL/USART3_TX_21") (pintype "passive+no_connect"))
    )
    (net (code "74") (name "unconnected-(U1-PB11{slash}I2C2_SDA{slash}USART3_RX-Pad22)") (class "Default")
      (node (ref "U1") (pin "22") (pinfunction "PB11/I2C2_SDA/USART3_RX_22") (pintype "passive+no_connect"))
    )
    (net (code "75") (name "unconnected-(U1-PB12{slash}SPI2_NSS{slash}TIM1_BKIN-Pad25)") (class "Default")
      (node (ref "U1") (pin "25") (pinfunction "PB12/SPI2_NSS/TIM1_BKIN_25") (pintype "passive"))
    )
    (net (code "76") (name "unconnected-(U1-PB13{slash}SPI2_SCK{slash}TIM1_CH1N-Pad26)") (class "Default")
      (node (ref "U1") (pin "26") (pinfunction "PB13/SPI2_SCK/TIM1_CH1N_26") (pintype "passive"))
    )
    (net (code "77") (name "unconnected-(U1-PB14{slash}SPI2_MISO{slash}TIM1_CH2N-Pad27)") (class "Default")
      (node (ref "U1") (pin "27") (pinfunction "PB14/SPI2_MISO/TIM1_CH2N_27") (pintype "passive"))
    )
    (net (code "78") (name "unconnected-(U1-PB15{slash}SPI2_MOSI{slash}TIM1_CH3N-Pad28)") (class "Default")
      (node (ref "U1") (pin "28") (pinfunction "PB15/SPI2_MOSI/TIM1_CH3N_28") (pintype "passive"))
    )
    (net (code "79") (name "unconnected-(U1-PC13-ANTI_TAMP-Pad2)") (class "Default")
      (node (ref "U1") (pin "2") (pinfunction "PC13-ANTI_TAMP_2") (pintype "passive"))
    )
    (net (code "80") (name "unconnected-(U1-PC14-OSC32_IN-Pad3)") (class "Default")
      (node (ref "U1") (pin "3") (pinfunction "PC14-OSC32_IN_3") (pintype "passive"))
    )
    (net (code "81") (name "unconnected-(U1-PC15-OSC32_OUT-Pad4)") (class "Default")
      (node (ref "U1") (pin "4") (pinfunction "PC15-OSC32_OUT_4") (pintype "passive"))
    )
    (net (code "82") (name "unconnected-(U4-Vref-Pad5)") (class "Default")
      (node (ref "U4") (pin "5") (pinfunction "Vref_5") (pintype "passive+no_connect"))
    )
  )
)
